# BUS_4TEE_1.net
KiCad netlist of a schematic drawn in EAGLE
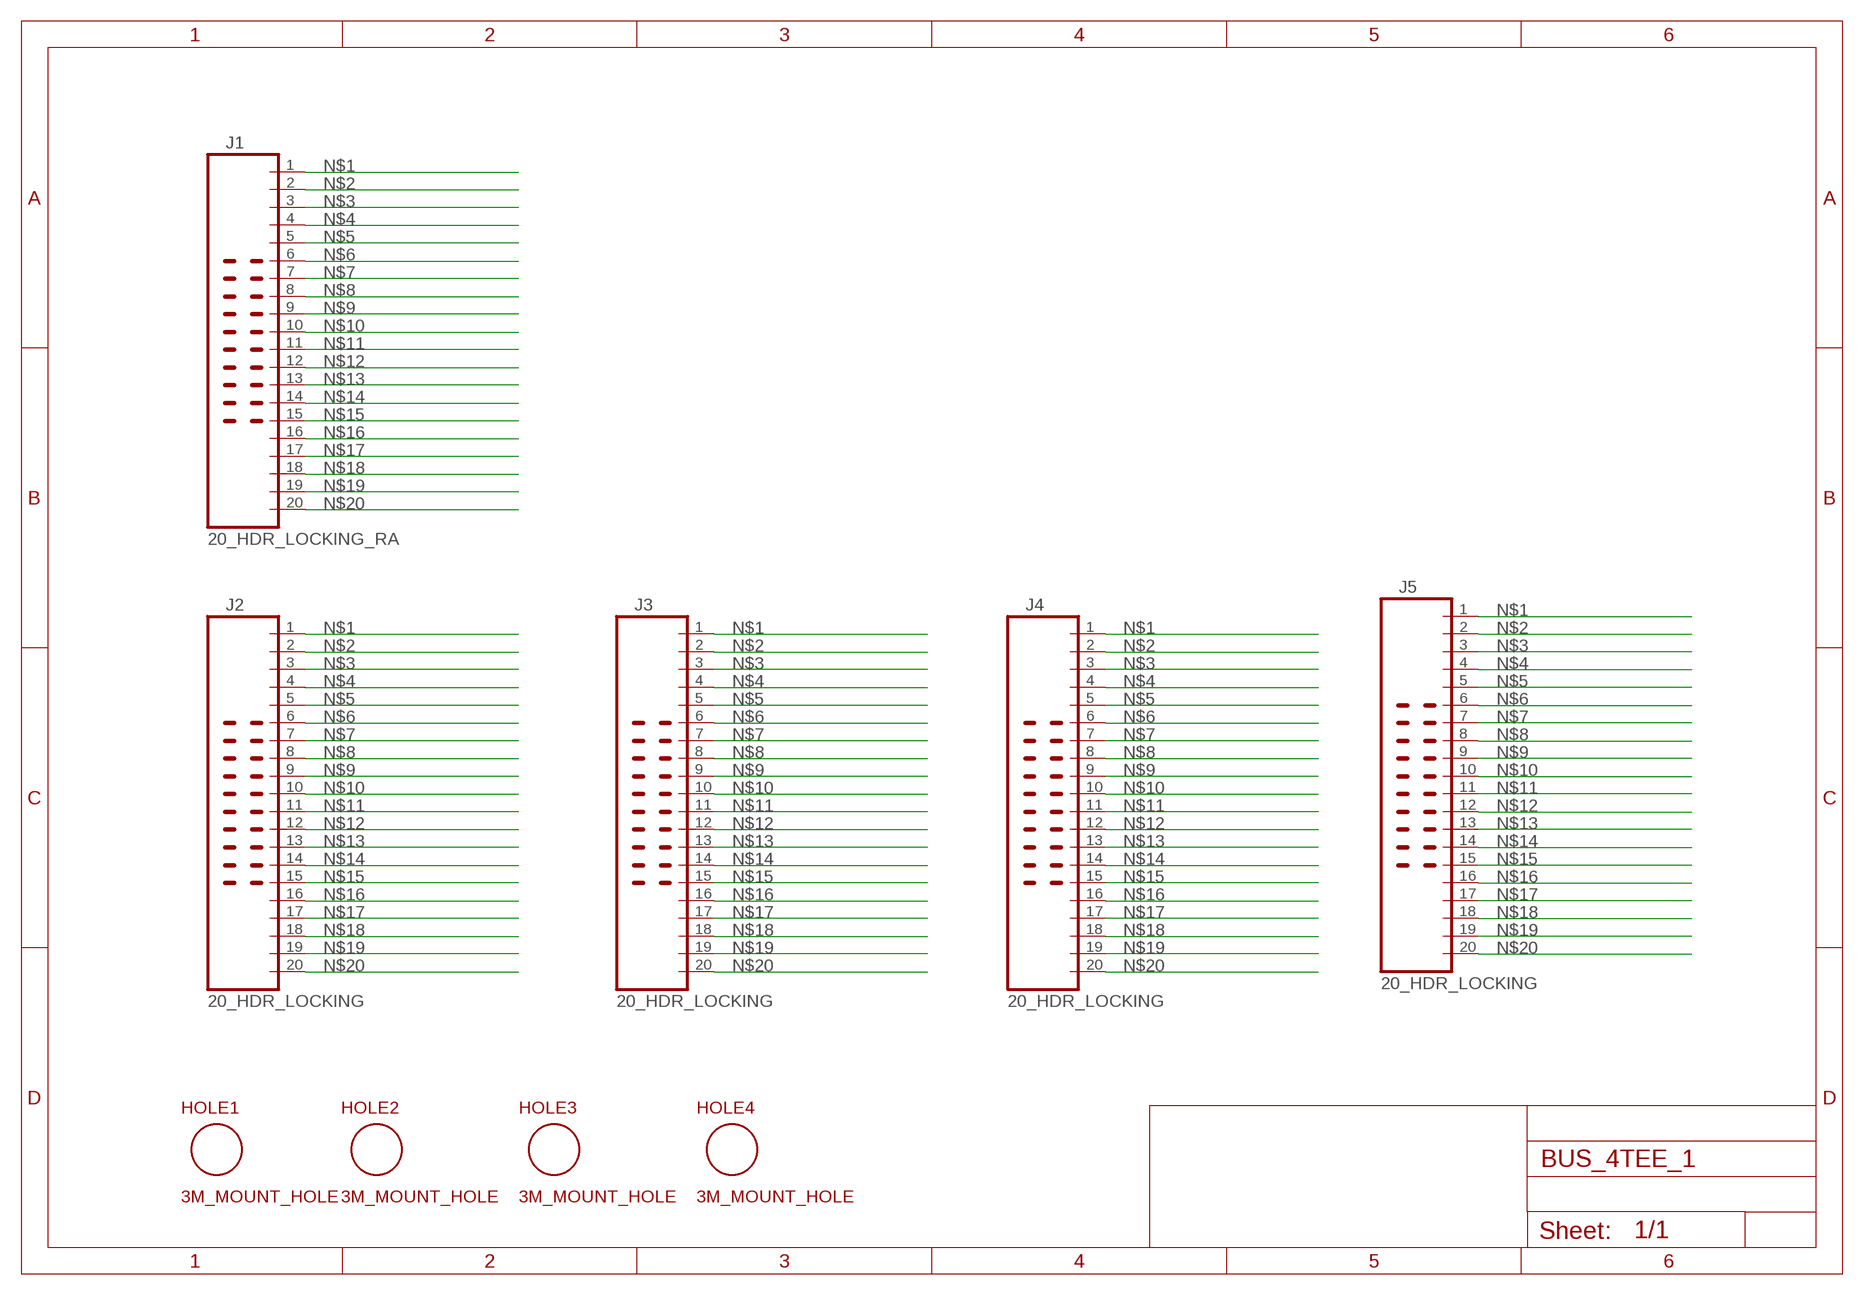
[diagram p0: schematic, sheet 1]

(export (version "E")
  (design (tool "Eeschema 10.0.6"))
  (components
    (comp (ref "HOLE1")
      (value "3M_MOUNT_HOLE")
      (footprint "eagle-import:3M_HOLE")
      (libsource (lib "eagle-import") (part "3M_MOUNT_HOLE"))
    )
    (comp (ref "HOLE2")
      (value "3M_MOUNT_HOLE")
      (footprint "eagle-import:3M_HOLE")
      (libsource (lib "eagle-import") (part "3M_MOUNT_HOLE"))
    )
    (comp (ref "HOLE3")
      (value "3M_MOUNT_HOLE")
      (footprint "eagle-import:3M_HOLE")
      (libsource (lib "eagle-import") (part "3M_MOUNT_HOLE"))
    )
    (comp (ref "HOLE4")
      (value "3M_MOUNT_HOLE")
      (footprint "eagle-import:3M_HOLE")
      (libsource (lib "eagle-import") (part "3M_MOUNT_HOLE"))
    )
    (comp (ref "J1")
      (value "20_HDR_LOCKING_RA")
      (footprint "eagle-import:20_HDR_LOCKING_RA")
      (libsource (lib "eagle-import") (part "20_HDR_LOCKING_RA"))
    )
    (comp (ref "J2")
      (value "20_HDR_LOCKING")
      (footprint "eagle-import:20_HDR_LOCKING")
      (libsource (lib "eagle-import") (part "20_HDR_LOCKING"))
    )
    (comp (ref "J3")
      (value "20_HDR_LOCKING")
      (footprint "eagle-import:20_HDR_LOCKING")
      (libsource (lib "eagle-import") (part "20_HDR_LOCKING"))
    )
    (comp (ref "J4")
      (value "20_HDR_LOCKING")
      (footprint "eagle-import:20_HDR_LOCKING")
      (libsource (lib "eagle-import") (part "20_HDR_LOCKING"))
    )
    (comp (ref "J5")
      (value "20_HDR_LOCKING")
      (footprint "eagle-import:20_HDR_LOCKING")
      (libsource (lib "eagle-import") (part "20_HDR_LOCKING"))
    )
  )
  (nets
    (net (code "1") (name "/N$1") (class "Default")
      (node (ref "J1") (pin "1") (pinfunction "1_1") (pintype "bidirectional"))
      (node (ref "J2") (pin "1") (pinfunction "1_1") (pintype "bidirectional"))
      (node (ref "J3") (pin "1") (pinfunction "1_1") (pintype "bidirectional"))
      (node (ref "J4") (pin "1") (pinfunction "1_1") (pintype "bidirectional"))
      (node (ref "J5") (pin "1") (pinfunction "1_1") (pintype "bidirectional"))
    )
    (net (code "2") (name "/N$2") (class "Default")
      (node (ref "J1") (pin "2") (pinfunction "2_2") (pintype "bidirectional"))
      (node (ref "J2") (pin "2") (pinfunction "2_2") (pintype "bidirectional"))
      (node (ref "J3") (pin "2") (pinfunction "2_2") (pintype "bidirectional"))
      (node (ref "J4") (pin "2") (pinfunction "2_2") (pintype "bidirectional"))
      (node (ref "J5") (pin "2") (pinfunction "2_2") (pintype "bidirectional"))
    )
    (net (code "3") (name "/N$3") (class "Default")
      (node (ref "J1") (pin "3") (pinfunction "3_3") (pintype "bidirectional"))
      (node (ref "J2") (pin "3") (pinfunction "3_3") (pintype "bidirectional"))
      (node (ref "J3") (pin "3") (pinfunction "3_3") (pintype "bidirectional"))
      (node (ref "J4") (pin "3") (pinfunction "3_3") (pintype "bidirectional"))
      (node (ref "J5") (pin "3") (pinfunction "3_3") (pintype "bidirectional"))
    )
    (net (code "4") (name "/N$4") (class "Default")
      (node (ref "J1") (pin "4") (pinfunction "4_4") (pintype "bidirectional"))
      (node (ref "J2") (pin "4") (pinfunction "4_4") (pintype "bidirectional"))
      (node (ref "J3") (pin "4") (pinfunction "4_4") (pintype "bidirectional"))
      (node (ref "J4") (pin "4") (pinfunction "4_4") (pintype "bidirectional"))
      (node (ref "J5") (pin "4") (pinfunction "4_4") (pintype "bidirectional"))
    )
    (net (code "5") (name "/N$5") (class "Default")
      (node (ref "J1") (pin "5") (pinfunction "5_5") (pintype "bidirectional"))
      (node (ref "J2") (pin "5") (pinfunction "5_5") (pintype "bidirectional"))
      (node (ref "J3") (pin "5") (pinfunction "5_5") (pintype "bidirectional"))
      (node (ref "J4") (pin "5") (pinfunction "5_5") (pintype "bidirectional"))
      (node (ref "J5") (pin "5") (pinfunction "5_5") (pintype "bidirectional"))
    )
    (net (code "6") (name "/N$6") (class "Default")
      (node (ref "J1") (pin "6") (pinfunction "6_6") (pintype "bidirectional"))
      (node (ref "J2") (pin "6") (pinfunction "6_6") (pintype "bidirectional"))
      (node (ref "J3") (pin "6") (pinfunction "6_6") (pintype "bidirectional"))
      (node (ref "J4") (pin "6") (pinfunction "6_6") (pintype "bidirectional"))
      (node (ref "J5") (pin "6") (pinfunction "6_6") (pintype "bidirectional"))
    )
    (net (code "7") (name "/N$7") (class "Default")
      (node (ref "J1") (pin "7") (pinfunction "7_7") (pintype "bidirectional"))
      (node (ref "J2") (pin "7") (pinfunction "7_7") (pintype "bidirectional"))
      (node (ref "J3") (pin "7") (pinfunction "7_7") (pintype "bidirectional"))
      (node (ref "J4") (pin "7") (pinfunction "7_7") (pintype "bidirectional"))
      (node (ref "J5") (pin "7") (pinfunction "7_7") (pintype "bidirectional"))
    )
    (net (code "8") (name "/N$8") (class "Default")
      (node (ref "J1") (pin "8") (pinfunction "8_8") (pintype "bidirectional"))
      (node (ref "J2") (pin "8") (pinfunction "8_8") (pintype "bidirectional"))
      (node (ref "J3") (pin "8") (pinfunction "8_8") (pintype "bidirectional"))
      (node (ref "J4") (pin "8") (pinfunction "8_8") (pintype "bidirectional"))
      (node (ref "J5") (pin "8") (pinfunction "8_8") (pintype "bidirectional"))
    )
    (net (code "9") (name "/N$9") (class "Default")
      (node (ref "J1") (pin "9") (pinfunction "9_9") (pintype "bidirectional"))
      (node (ref "J2") (pin "9") (pinfunction "9_9") (pintype "bidirectional"))
      (node (ref "J3") (pin "9") (pinfunction "9_9") (pintype "bidirectional"))
      (node (ref "J4") (pin "9") (pinfunction "9_9") (pintype "bidirectional"))
      (node (ref "J5") (pin "9") (pinfunction "9_9") (pintype "bidirectional"))
    )
    (net (code "10") (name "/N$10") (class "Default")
      (node (ref "J1") (pin "10") (pinfunction "10_10") (pintype "bidirectional"))
      (node (ref "J2") (pin "10") (pinfunction "10_10") (pintype "bidirectional"))
      (node (ref "J3") (pin "10") (pinfunction "10_10") (pintype "bidirectional"))
      (node (ref "J4") (pin "10") (pinfunction "10_10") (pintype "bidirectional"))
      (node (ref "J5") (pin "10") (pinfunction "10_10") (pintype "bidirectional"))
    )
    (net (code "11") (name "/N$11") (class "Default")
      (node (ref "J1") (pin "11") (pinfunction "11_11") (pintype "bidirectional"))
      (node (ref "J2") (pin "11") (pinfunction "11_11") (pintype "bidirectional"))
      (node (ref "J3") (pin "11") (pinfunction "11_11") (pintype "bidirectional"))
      (node (ref "J4") (pin "11") (pinfunction "11_11") (pintype "bidirectional"))
      (node (ref "J5") (pin "11") (pinfunction "11_11") (pintype "bidirectional"))
    )
    (net (code "12") (name "/N$12") (class "Default")
      (node (ref "J1") (pin "12") (pinfunction "12_12") (pintype "bidirectional"))
      (node (ref "J2") (pin "12") (pinfunction "12_12") (pintype "bidirectional"))
      (node (ref "J3") (pin "12") (pinfunction "12_12") (pintype "bidirectional"))
      (node (ref "J4") (pin "12") (pinfunction "12_12") (pintype "bidirectional"))
      (node (ref "J5") (pin "12") (pinfunction "12_12") (pintype "bidirectional"))
    )
    (net (code "13") (name "/N$13") (class "Default")
      (node (ref "J1") (pin "13") (pinfunction "13_13") (pintype "bidirectional"))
      (node (ref "J2") (pin "13") (pinfunction "13_13") (pintype "bidirectional"))
      (node (ref "J3") (pin "13") (pinfunction "13_13") (pintype "bidirectional"))
      (node (ref "J4") (pin "13") (pinfunction "13_13") (pintype "bidirectional"))
      (node (ref "J5") (pin "13") (pinfunction "13_13") (pintype "bidirectional"))
    )
    (net (code "14") (name "/N$14") (class "Default")
      (node (ref "J1") (pin "14") (pinfunction "14_14") (pintype "bidirectional"))
      (node (ref "J2") (pin "14") (pinfunction "14_14") (pintype "bidirectional"))
      (node (ref "J3") (pin "14") (pinfunction "14_14") (pintype "bidirectional"))
      (node (ref "J4") (pin "14") (pinfunction "14_14") (pintype "bidirectional"))
      (node (ref "J5") (pin "14") (pinfunction "14_14") (pintype "bidirectional"))
    )
    (net (code "15") (name "/N$15") (class "Default")
      (node (ref "J1") (pin "15") (pinfunction "15_15") (pintype "bidirectional"))
      (node (ref "J2") (pin "15") (pinfunction "15_15") (pintype "bidirectional"))
      (node (ref "J3") (pin "15") (pinfunction "15_15") (pintype "bidirectional"))
      (node (ref "J4") (pin "15") (pinfunction "15_15") (pintype "bidirectional"))
      (node (ref "J5") (pin "15") (pinfunction "15_15") (pintype "bidirectional"))
    )
    (net (code "16") (name "/N$16") (class "Default")
      (node (ref "J1") (pin "16") (pinfunction "16_16") (pintype "bidirectional"))
      (node (ref "J2") (pin "16") (pinfunction "16_16") (pintype "bidirectional"))
      (node (ref "J3") (pin "16") (pinfunction "16_16") (pintype "bidirectional"))
      (node (ref "J4") (pin "16") (pinfunction "16_16") (pintype "bidirectional"))
      (node (ref "J5") (pin "16") (pinfunction "16_16") (pintype "bidirectional"))
    )
    (net (code "17") (name "/N$17") (class "Default")
      (node (ref "J1") (pin "17") (pinfunction "17_17") (pintype "bidirectional"))
      (node (ref "J2") (pin "17") (pinfunction "17_17") (pintype "bidirectional"))
      (node (ref "J3") (pin "17") (pinfunction "17_17") (pintype "bidirectional"))
      (node (ref "J4") (pin "17") (pinfunction "17_17") (pintype "bidirectional"))
      (node (ref "J5") (pin "17") (pinfunction "17_17") (pintype "bidirectional"))
    )
    (net (code "18") (name "/N$18") (class "Default")
      (node (ref "J1") (pin "18") (pinfunction "18_18") (pintype "bidirectional"))
      (node (ref "J2") (pin "18") (pinfunction "18_18") (pintype "bidirectional"))
      (node (ref "J3") (pin "18") (pinfunction "18_18") (pintype "bidirectional"))
      (node (ref "J4") (pin "18") (pinfunction "18_18") (pintype "bidirectional"))
      (node (ref "J5") (pin "18") (pinfunction "18_18") (pintype "bidirectional"))
    )
    (net (code "19") (name "/N$19") (class "Default")
      (node (ref "J1") (pin "19") (pinfunction "19_19") (pintype "bidirectional"))
      (node (ref "J2") (pin "19") (pinfunction "19_19") (pintype "bidirectional"))
      (node (ref "J3") (pin "19") (pinfunction "19_19") (pintype "bidirectional"))
      (node (ref "J4") (pin "19") (pinfunction "19_19") (pintype "bidirectional"))
      (node (ref "J5") (pin "19") (pinfunction "19_19") (pintype "bidirectional"))
    )
    (net (code "20") (name "/N$20") (class "Default")
      (node (ref "J1") (pin "20") (pinfunction "20_20") (pintype "bidirectional"))
      (node (ref "J2") (pin "20") (pinfunction "20_20") (pintype "bidirectional"))
      (node (ref "J3") (pin "20") (pinfunction "20_20") (pintype "bidirectional"))
      (node (ref "J4") (pin "20") (pinfunction "20_20") (pintype "bidirectional"))
      (node (ref "J5") (pin "20") (pinfunction "20_20") (pintype "bidirectional"))
    )
  )
)
